# A4a_CubeCell.net
KiCad netlist of a schematic drawn in EAGLE
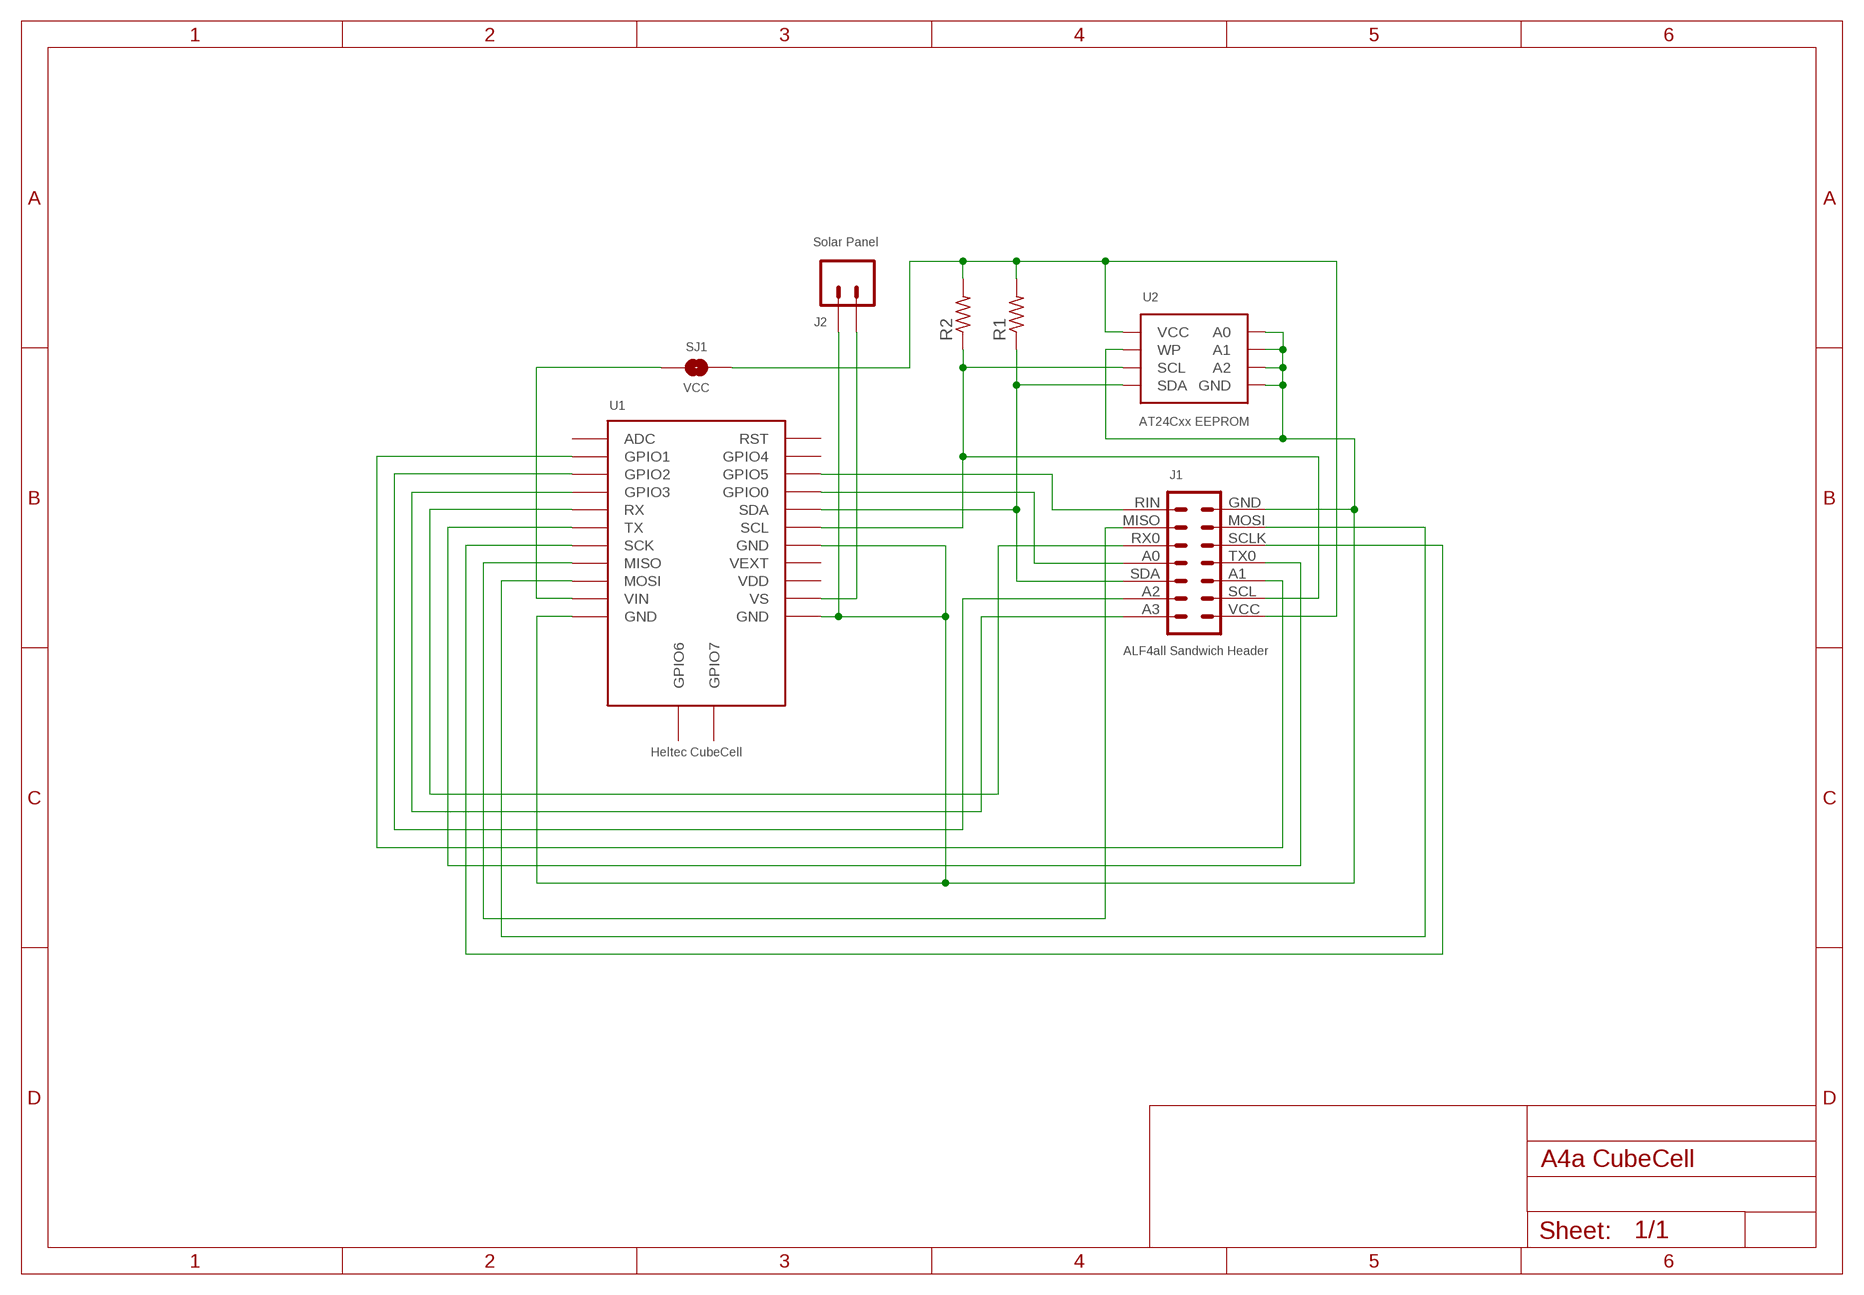
[diagram p0: schematic, sheet 1]

(export (version "E")
  (design (tool "Eeschema 10.0.6"))
  (components
    (comp (ref "J1")
      (value "ALF4all Sandwich Header")
      (footprint "eagle-import:CONN_2X7-ALF4ALL-PROCESSOR-B")
      (libsource (lib "eagle-import") (part "HEADER-2X7-ALF4ALL-PROCESSOR-B"))
    )
    (comp (ref "J2")
      (value "Solar Panel")
      (footprint "eagle-import:JST-PH2.0-2-HORIZONTAL")
      (libsource (lib "eagle-import") (part "JST-PH2.0-2-MALE-HORIZONTALJST-PTH-2"))
    )
    (comp (ref "R1")
      (value "RESISTORR0805")
      (footprint "eagle-import:R0805")
      (libsource (lib "eagle-import") (part "RESISTORR0805"))
    )
    (comp (ref "R2")
      (value "RESISTORR0805")
      (footprint "eagle-import:R0805")
      (libsource (lib "eagle-import") (part "RESISTORR0805"))
    )
    (comp (ref "SJ1")
      (value "VCC")
      (footprint "eagle-import:SJ")
      (libsource (lib "eagle-import") (part "SJ"))
    )
    (comp (ref "U1")
      (value "Heltec CubeCell")
      (footprint "eagle-import:HELTEC-CUBECELL")
      (libsource (lib "eagle-import") (part "HELTEC-CUBECELL"))
    )
    (comp (ref "U2")
      (value "AT24Cxx EEPROM")
      (footprint "eagle-import:SOP-8-WITH-VIAS-4-5")
      (libsource (lib "eagle-import") (part "AT24CXX-EEPROM-VIAS-4-5"))
    )
  )
  (nets
    (net (code "1") (name "Net-(J1-1)") (class "Default")
      (node (ref "J1") (pin "VCC") (pinfunction "1_VCC") (pintype "passive"))
      (node (ref "R1") (pin "2") (pinfunction "2_2") (pintype "passive"))
      (node (ref "R2") (pin "2") (pinfunction "2_2") (pintype "passive"))
      (node (ref "SJ1") (pin "2") (pinfunction "2_2") (pintype "passive"))
      (node (ref "U2") (pin "P$8") (pinfunction "VCC_P$8") (pintype "bidirectional"))
    )
    (net (code "2") (name "Net-(J1-2)") (class "Default")
      (node (ref "J1") (pin "SCL") (pinfunction "2_SCL") (pintype "passive"))
      (node (ref "R2") (pin "1") (pinfunction "1_1") (pintype "passive"))
      (node (ref "U1") (pin "SCL") (pinfunction "SCL_SCL") (pintype "bidirectional"))
      (node (ref "U2") (pin "P$6") (pinfunction "SCL_P$6") (pintype "bidirectional"))
    )
    (net (code "3") (name "Net-(J1-3)") (class "Default")
      (node (ref "J1") (pin "A1") (pinfunction "3_A1") (pintype "passive"))
      (node (ref "U1") (pin "GPIO1") (pinfunction "GPIO1_GPIO1") (pintype "bidirectional"))
    )
    (net (code "4") (name "Net-(J1-4)") (class "Default")
      (node (ref "J1") (pin "TX0") (pinfunction "4_TX0") (pintype "passive"))
      (node (ref "U1") (pin "TX") (pinfunction "TX_TX") (pintype "bidirectional"))
    )
    (net (code "5") (name "Net-(J1-5)") (class "Default")
      (node (ref "J1") (pin "SCLK") (pinfunction "5_SCLK") (pintype "passive"))
      (node (ref "U1") (pin "SCK") (pinfunction "SCK_SCK") (pintype "bidirectional"))
    )
    (net (code "6") (name "Net-(J1-6)") (class "Default")
      (node (ref "J1") (pin "MOSI") (pinfunction "6_MOSI") (pintype "passive"))
      (node (ref "U1") (pin "MOSI") (pinfunction "MOSI_MOSI") (pintype "bidirectional"))
    )
    (net (code "7") (name "Net-(J1-7)") (class "Default")
      (node (ref "J1") (pin "GND") (pinfunction "7_GND") (pintype "passive"))
      (node (ref "J2") (pin "-") (pinfunction "1_-") (pintype "passive"))
      (node (ref "U1") (pin "GND@11") (pinfunction "GND_GND@11") (pintype "bidirectional"))
      (node (ref "U1") (pin "GND@14") (pinfunction "GND_GND@14") (pintype "bidirectional"))
      (node (ref "U1") (pin "GND@18") (pinfunction "GND_GND@18") (pintype "bidirectional"))
      (node (ref "U2") (pin "P$1") (pinfunction "A0_P$1") (pintype "bidirectional"))
      (node (ref "U2") (pin "P$2") (pinfunction "A1_P$2") (pintype "bidirectional"))
      (node (ref "U2") (pin "P$3") (pinfunction "A2_P$3") (pintype "bidirectional"))
      (node (ref "U2") (pin "P$4") (pinfunction "GND_P$4") (pintype "bidirectional"))
      (node (ref "U2") (pin "P$4@VIA") (pinfunction "GND_P$4@VIA") (pintype "bidirectional"))
      (node (ref "U2") (pin "P$7") (pinfunction "WP_P$7") (pintype "bidirectional"))
    )
    (net (code "8") (name "Net-(J1-8)") (class "Default")
      (node (ref "J1") (pin "RIN") (pinfunction "8_RIN") (pintype "passive"))
      (node (ref "U1") (pin "GPIO5") (pinfunction "GPIO5_GPIO5") (pintype "bidirectional"))
    )
    (net (code "9") (name "Net-(J1-9)") (class "Default")
      (node (ref "J1") (pin "MISO") (pinfunction "9_MISO") (pintype "passive"))
      (node (ref "U1") (pin "MISO") (pinfunction "MISO_MISO") (pintype "bidirectional"))
    )
    (net (code "10") (name "Net-(J1-10)") (class "Default")
      (node (ref "J1") (pin "RX0") (pinfunction "10_RX0") (pintype "passive"))
      (node (ref "U1") (pin "RX") (pinfunction "RX_RX") (pintype "bidirectional"))
    )
    (net (code "11") (name "Net-(J1-11)") (class "Default")
      (node (ref "J1") (pin "A0") (pinfunction "11_A0") (pintype "passive"))
      (node (ref "U1") (pin "GPIO0") (pinfunction "GPIO0_GPIO0") (pintype "bidirectional"))
    )
    (net (code "12") (name "Net-(J1-12)") (class "Default")
      (node (ref "J1") (pin "SDA") (pinfunction "12_SDA") (pintype "passive"))
      (node (ref "R1") (pin "1") (pinfunction "1_1") (pintype "passive"))
      (node (ref "U1") (pin "SDA") (pinfunction "SDA_SDA") (pintype "bidirectional"))
      (node (ref "U2") (pin "P$5") (pinfunction "SDA_P$5") (pintype "bidirectional"))
      (node (ref "U2") (pin "P$5@VIA") (pinfunction "SDA_P$5@VIA") (pintype "bidirectional"))
    )
    (net (code "13") (name "Net-(J1-13)") (class "Default")
      (node (ref "J1") (pin "A2") (pinfunction "13_A2") (pintype "passive"))
      (node (ref "U1") (pin "GPIO2") (pinfunction "GPIO2_GPIO2") (pintype "bidirectional"))
    )
    (net (code "14") (name "Net-(J1-14)") (class "Default")
      (node (ref "J1") (pin "A3") (pinfunction "14_A3") (pintype "passive"))
      (node (ref "U1") (pin "GPIO3") (pinfunction "GPIO3_GPIO3") (pintype "bidirectional"))
    )
    (net (code "15") (name "Net-(J2-2)") (class "Default")
      (node (ref "J2") (pin "+") (pinfunction "2_+") (pintype "passive"))
      (node (ref "U1") (pin "VS") (pinfunction "VS_VS") (pintype "bidirectional"))
    )
    (net (code "16") (name "Net-(SJ1-Pad1)") (class "Default")
      (node (ref "SJ1") (pin "1") (pinfunction "1_1") (pintype "passive"))
      (node (ref "U1") (pin "VIN") (pinfunction "VIN_VIN") (pintype "bidirectional"))
    )
    (net (code "17") (name "unconnected-(U1-PadADC)") (class "Default")
      (node (ref "U1") (pin "ADC") (pinfunction "ADC_ADC") (pintype "bidirectional"))
    )
    (net (code "18") (name "unconnected-(U1-PadGPIO4)") (class "Default")
      (node (ref "U1") (pin "GPIO4") (pinfunction "GPIO4_GPIO4") (pintype "bidirectional"))
    )
    (net (code "19") (name "unconnected-(U1-PadGPIO6)") (class "Default")
      (node (ref "U1") (pin "GPIO6") (pinfunction "GPIO6_GPIO6") (pintype "bidirectional"))
    )
    (net (code "20") (name "unconnected-(U1-PadGPIO7)") (class "Default")
      (node (ref "U1") (pin "GPIO7") (pinfunction "GPIO7_GPIO7") (pintype "bidirectional"))
    )
    (net (code "21") (name "unconnected-(U1-PadRST)") (class "Default")
      (node (ref "U1") (pin "RST") (pinfunction "RST_RST") (pintype "bidirectional"))
    )
    (net (code "22") (name "unconnected-(U1-PadVDD)") (class "Default")
      (node (ref "U1") (pin "VDD") (pinfunction "VDD_VDD") (pintype "bidirectional"))
    )
    (net (code "23") (name "unconnected-(U1-PadVEXT)") (class "Default")
      (node (ref "U1") (pin "VEXT") (pinfunction "VEXT_VEXT") (pintype "bidirectional"))
    )
  )
)
